# ME433_First_PCB.net
KiCad netlist of a schematic drawn in EAGLE
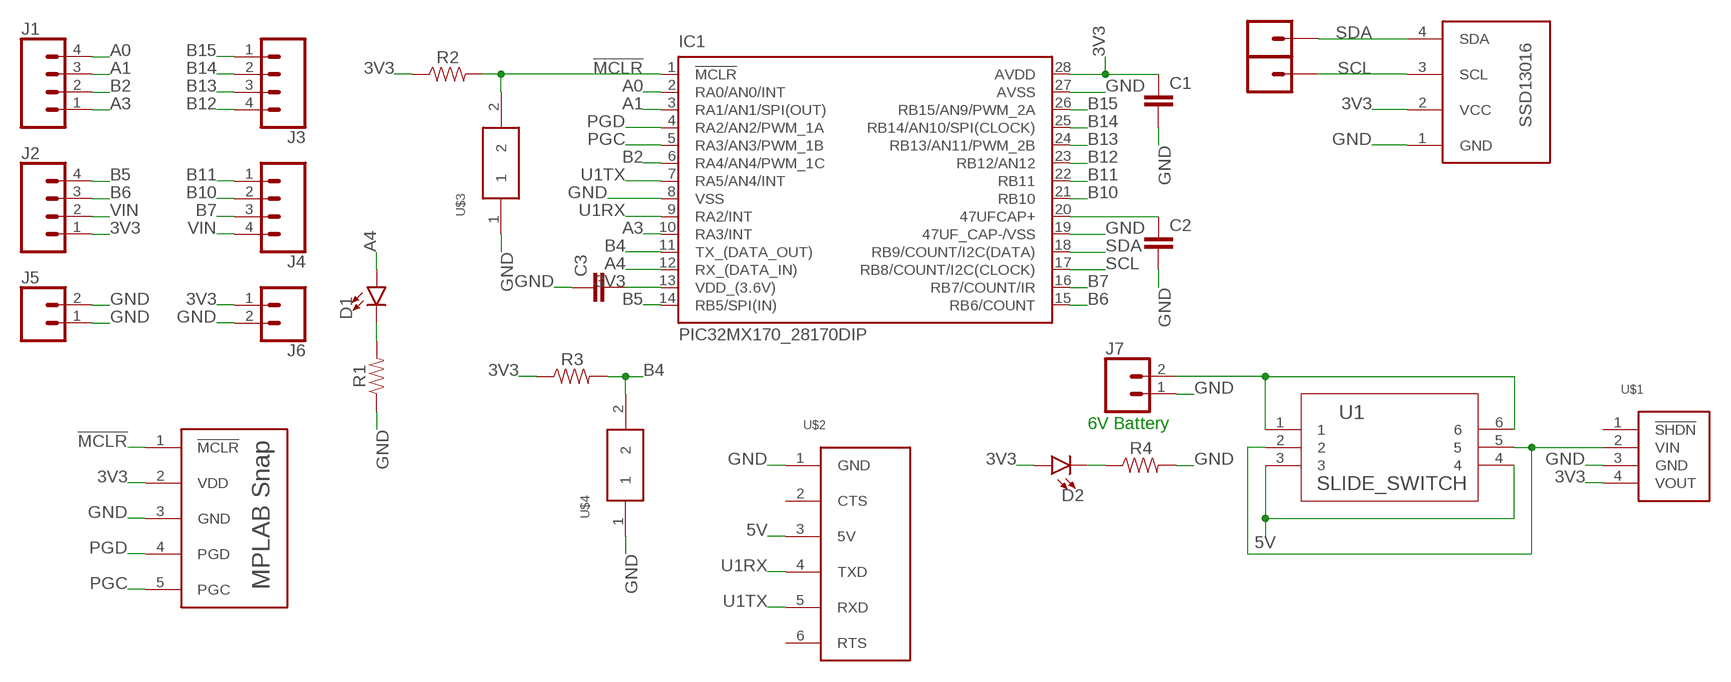
[diagram p0: schematic, sheet 1]

(export (version "E")
  (design (tool "Eeschema 10.0.6"))
  (components
    (comp (ref "C1")
      (value "C-EU025-025X050")
      (footprint "eagle-import:C025-025X050")
      (libsource (lib "eagle-import") (part "C-EU025-025X050"))
    )
    (comp (ref "C2")
      (value "C-EU025-025X050")
      (footprint "eagle-import:C025-025X050")
      (libsource (lib "eagle-import") (part "C-EU025-025X050"))
    )
    (comp (ref "C3")
      (value "C-EU025-025X050")
      (footprint "eagle-import:C025-025X050")
      (libsource (lib "eagle-import") (part "C-EU025-025X050"))
    )
    (comp (ref "D1")
      (value "LED3MM")
      (footprint "eagle-import:LED_3MM")
      (libsource (lib "eagle-import") (part "LED3MM"))
    )
    (comp (ref "D2")
      (value "LED3MM")
      (footprint "eagle-import:LED_3MM")
      (libsource (lib "eagle-import") (part "LED3MM"))
    )
    (comp (ref "IC1")
      (value "PIC32MX170_28170DIP")
      (footprint "eagle-import:DIL28-3")
      (libsource (lib "eagle-import") (part "PIC32MX170_28DIP170"))
    )
    (comp (ref "J1")
      (value "CONN_04")
      (footprint "eagle-import:1X04")
      (libsource (lib "eagle-import") (part "CONN_04"))
    )
    (comp (ref "J2")
      (value "CONN_04")
      (footprint "eagle-import:1X04")
      (libsource (lib "eagle-import") (part "CONN_04"))
    )
    (comp (ref "J3")
      (value "CONN_04")
      (footprint "eagle-import:1X04")
      (libsource (lib "eagle-import") (part "CONN_04"))
    )
    (comp (ref "J4")
      (value "CONN_04")
      (footprint "eagle-import:1X04")
      (libsource (lib "eagle-import") (part "CONN_04"))
    )
    (comp (ref "J5")
      (value "CONN_02")
      (footprint "eagle-import:1X02")
      (libsource (lib "eagle-import") (part "CONN_02"))
    )
    (comp (ref "J6")
      (value "CONN_02")
      (footprint "eagle-import:1X02")
      (libsource (lib "eagle-import") (part "CONN_02"))
    )
    (comp (ref "J7")
      (value "CONN_02")
      (footprint "eagle-import:1X02")
      (libsource (lib "eagle-import") (part "CONN_02"))
    )
    (comp (ref "J8")
      (value "CONN_01")
      (footprint "eagle-import:1X01")
      (libsource (lib "eagle-import") (part "CONN_01"))
    )
    (comp (ref "J9")
      (value "CONN_01")
      (footprint "eagle-import:1X01")
      (libsource (lib "eagle-import") (part "CONN_01"))
    )
    (comp (ref "OLED")
      (value "OLED_SCREEN")
      (footprint "eagle-import:OLED_SCREEN")
      (libsource (lib "eagle-import") (part "OLED_SCREEN"))
    )
    (comp (ref "R1")
      (value "1M")
      (footprint "eagle-import:AXIAL-0.3")
      (libsource (lib "eagle-import") (part "1MOHM-HORIZ-1/4W-5%"))
    )
    (comp (ref "R2")
      (value "1M")
      (footprint "eagle-import:AXIAL-0.3")
      (libsource (lib "eagle-import") (part "1MOHM-HORIZ-1/4W-5%"))
    )
    (comp (ref "R3")
      (value "1M")
      (footprint "eagle-import:AXIAL-0.3")
      (libsource (lib "eagle-import") (part "1MOHM-HORIZ-1/4W-5%"))
    )
    (comp (ref "R4")
      (value "1M")
      (footprint "eagle-import:AXIAL-0.3")
      (libsource (lib "eagle-import") (part "1MOHM-HORIZ-1/4W-5%"))
    )
    (comp (ref "U$1")
      (value "POLOLU_3V3_VREG")
      (footprint "eagle-import:POLOLU_3V3_VREG")
      (libsource (lib "eagle-import") (part "POLOLU_3V3_VREG"))
    )
    (comp (ref "U$2")
      (value "ADAFRUIT_CP2104")
      (footprint "eagle-import:ADAFRUIT_CP2104")
      (libsource (lib "eagle-import") (part "ADAFRUIT_CP2104"))
    )
    (comp (ref "U$3")
      (value "BUTTON")
      (footprint "eagle-import:BUTTON")
      (libsource (lib "eagle-import") (part "BUTTON"))
    )
    (comp (ref "U$4")
      (value "BUTTON")
      (footprint "eagle-import:BUTTON")
      (libsource (lib "eagle-import") (part "BUTTON"))
    )
    (comp (ref "U$5")
      (value "MPLAB_SNAP")
      (footprint "eagle-import:MPLAB_SNAP")
      (libsource (lib "eagle-import") (part "MPLAB_SNAP"))
    )
    (comp (ref "U1")
      (value "SLIDE_SWITCH")
      (footprint "eagle-import:SWITCH_011CQN")
      (fields
        (field (name "MANUFACTURER_PART_NUMBER") "JS202011CQN")
        (field (name "COPYRIGHT") "Copyright (C) 2022 Ultra Librarian. All rights reserved.")
      )
      (libsource (lib "eagle-import") (part "SLIDE_SWITCH"))
    )
  )
  (nets
    (net (code "1") (name "/3V3") (class "Default")
      (node (ref "C1") (pin "1") (pinfunction "1_1") (pintype "passive"))
      (node (ref "C3") (pin "2") (pinfunction "2_2") (pintype "passive"))
      (node (ref "D2") (pin "A") (pinfunction "A_A") (pintype "passive"))
      (node (ref "IC1") (pin "13") (pinfunction "VDD_(3.6V)_13") (pintype "bidirectional"))
      (node (ref "IC1") (pin "28") (pinfunction "AVDD_28") (pintype "bidirectional"))
      (node (ref "J2") (pin "1") (pinfunction "1_1") (pintype "passive"))
      (node (ref "J6") (pin "1") (pinfunction "1_1") (pintype "passive"))
      (node (ref "OLED") (pin "2") (pinfunction "VCC_2") (pintype "bidirectional"))
      (node (ref "R2") (pin "P$1") (pinfunction "1_P$1") (pintype "passive"))
      (node (ref "R3") (pin "P$1") (pinfunction "1_P$1") (pintype "passive"))
      (node (ref "U$1") (pin "4") (pinfunction "VOUT_4") (pintype "passive"))
      (node (ref "U$5") (pin "2") (pinfunction "VDD_2") (pintype "bidirectional"))
    )
    (net (code "2") (name "/5V") (class "Default")
      (node (ref "U$2") (pin "3") (pinfunction "5V_3") (pintype "bidirectional"))
      (node (ref "U1") (pin "3") (pinfunction "3_3") (pintype "passive"))
      (node (ref "U1") (pin "4") (pinfunction "4_4") (pintype "passive"))
    )
    (net (code "3") (name "/A0") (class "Default")
      (node (ref "IC1") (pin "2") (pinfunction "RA0/AN0/INT_2") (pintype "bidirectional"))
      (node (ref "J1") (pin "4") (pinfunction "4_4") (pintype "passive"))
    )
    (net (code "4") (name "/A1") (class "Default")
      (node (ref "IC1") (pin "3") (pinfunction "RA1/AN1/SPI(OUT)_3") (pintype "bidirectional"))
      (node (ref "J1") (pin "3") (pinfunction "3_3") (pintype "passive"))
    )
    (net (code "5") (name "/A3") (class "Default")
      (node (ref "IC1") (pin "10") (pinfunction "RA3/INT_10") (pintype "output"))
      (node (ref "J1") (pin "1") (pinfunction "1_1") (pintype "passive"))
    )
    (net (code "6") (name "/A4") (class "Default")
      (node (ref "D1") (pin "A") (pinfunction "A_A") (pintype "passive"))
      (node (ref "IC1") (pin "12") (pinfunction "RX_(DATA_IN)_12") (pintype "bidirectional"))
    )
    (net (code "7") (name "/B2") (class "Default")
      (node (ref "IC1") (pin "6") (pinfunction "RA4/AN4/PWM_1C_6") (pintype "bidirectional"))
      (node (ref "J1") (pin "2") (pinfunction "2_2") (pintype "passive"))
    )
    (net (code "8") (name "/B4") (class "Default")
      (node (ref "IC1") (pin "11") (pinfunction "TX_(DATA_OUT)_11") (pintype "bidirectional"))
      (node (ref "R3") (pin "P$2") (pinfunction "2_P$2") (pintype "passive"))
      (node (ref "U$4") (pin "2") (pinfunction "2_2") (pintype "bidirectional"))
    )
    (net (code "9") (name "/B5") (class "Default")
      (node (ref "IC1") (pin "14") (pinfunction "RB5/SPI(IN)_14") (pintype "bidirectional"))
      (node (ref "J2") (pin "4") (pinfunction "4_4") (pintype "passive"))
    )
    (net (code "10") (name "/B6") (class "Default")
      (node (ref "IC1") (pin "15") (pinfunction "RB6/COUNT_15") (pintype "bidirectional"))
      (node (ref "J2") (pin "3") (pinfunction "3_3") (pintype "passive"))
    )
    (net (code "11") (name "/B7") (class "Default")
      (node (ref "IC1") (pin "16") (pinfunction "RB7/COUNT/IR_16") (pintype "bidirectional"))
      (node (ref "J4") (pin "3") (pinfunction "3_3") (pintype "passive"))
    )
    (net (code "12") (name "/B10") (class "Default")
      (node (ref "IC1") (pin "21") (pinfunction "RB10_21") (pintype "bidirectional"))
      (node (ref "J4") (pin "2") (pinfunction "2_2") (pintype "passive"))
    )
    (net (code "13") (name "/B11") (class "Default")
      (node (ref "IC1") (pin "22") (pinfunction "RB11_22") (pintype "bidirectional"))
      (node (ref "J4") (pin "1") (pinfunction "1_1") (pintype "passive"))
    )
    (net (code "14") (name "/B12") (class "Default")
      (node (ref "IC1") (pin "23") (pinfunction "RB12/AN12_23") (pintype "bidirectional"))
      (node (ref "J3") (pin "4") (pinfunction "4_4") (pintype "passive"))
    )
    (net (code "15") (name "/B13") (class "Default")
      (node (ref "IC1") (pin "24") (pinfunction "RB13/AN11/PWM_2B_24") (pintype "bidirectional"))
      (node (ref "J3") (pin "3") (pinfunction "3_3") (pintype "passive"))
    )
    (net (code "16") (name "/B14") (class "Default")
      (node (ref "IC1") (pin "25") (pinfunction "RB14/AN10/SPI(CLOCK)_25") (pintype "bidirectional"))
      (node (ref "J3") (pin "2") (pinfunction "2_2") (pintype "passive"))
    )
    (net (code "17") (name "/B15") (class "Default")
      (node (ref "IC1") (pin "26") (pinfunction "RB15/AN9/PWM_2A_26") (pintype "bidirectional"))
      (node (ref "J3") (pin "1") (pinfunction "1_1") (pintype "passive"))
    )
    (net (code "18") (name "/GND") (class "Default")
      (node (ref "C1") (pin "2") (pinfunction "2_2") (pintype "passive"))
      (node (ref "C2") (pin "2") (pinfunction "2_2") (pintype "passive"))
      (node (ref "C3") (pin "1") (pinfunction "1_1") (pintype "passive"))
      (node (ref "IC1") (pin "19") (pinfunction "47UF_CAP-/VSS_19") (pintype "power_in"))
      (node (ref "IC1") (pin "27") (pinfunction "AVSS_27") (pintype "bidirectional"))
      (node (ref "IC1") (pin "8") (pinfunction "VSS_8") (pintype "power_in"))
      (node (ref "J5") (pin "1") (pinfunction "1_1") (pintype "passive"))
      (node (ref "J5") (pin "2") (pinfunction "2_2") (pintype "passive"))
      (node (ref "J6") (pin "2") (pinfunction "2_2") (pintype "passive"))
      (node (ref "J7") (pin "1") (pinfunction "1_1") (pintype "passive"))
      (node (ref "OLED") (pin "1") (pinfunction "GND_1") (pintype "bidirectional"))
      (node (ref "R1") (pin "P$1") (pinfunction "1_P$1") (pintype "passive"))
      (node (ref "R4") (pin "P$2") (pinfunction "2_P$2") (pintype "passive"))
      (node (ref "U$1") (pin "3") (pinfunction "GND_3") (pintype "passive"))
      (node (ref "U$2") (pin "1") (pinfunction "GND_1") (pintype "bidirectional"))
      (node (ref "U$3") (pin "1") (pinfunction "1_1") (pintype "bidirectional"))
      (node (ref "U$4") (pin "1") (pinfunction "1_1") (pintype "bidirectional"))
      (node (ref "U$5") (pin "3") (pinfunction "GND_3") (pintype "bidirectional"))
    )
    (net (code "19") (name "/PGC") (class "Default")
      (node (ref "IC1") (pin "5") (pinfunction "RA3/AN3/PWM_1B_5") (pintype "bidirectional"))
      (node (ref "U$5") (pin "5") (pinfunction "PGC_5") (pintype "bidirectional"))
    )
    (net (code "20") (name "/PGD") (class "Default")
      (node (ref "IC1") (pin "4") (pinfunction "RA2/AN2/PWM_1A_4") (pintype "bidirectional"))
      (node (ref "U$5") (pin "4") (pinfunction "PGD_4") (pintype "bidirectional"))
    )
    (net (code "21") (name "/SCL") (class "Default")
      (node (ref "IC1") (pin "17") (pinfunction "RB8/COUNT/I2C(CLOCK)_17") (pintype "bidirectional"))
      (node (ref "J9") (pin "1") (pinfunction "1_1") (pintype "passive"))
      (node (ref "OLED") (pin "3") (pinfunction "SCL_3") (pintype "bidirectional"))
    )
    (net (code "22") (name "/SDA") (class "Default")
      (node (ref "IC1") (pin "18") (pinfunction "RB9/COUNT/I2C(DATA)_18") (pintype "bidirectional"))
      (node (ref "J8") (pin "1") (pinfunction "1_1") (pintype "passive"))
      (node (ref "OLED") (pin "4") (pinfunction "SDA_4") (pintype "bidirectional"))
    )
    (net (code "23") (name "/U1RX") (class "Default")
      (node (ref "IC1") (pin "9") (pinfunction "RA2/INT_9") (pintype "input"))
      (node (ref "U$2") (pin "4") (pinfunction "TXD_4") (pintype "bidirectional"))
    )
    (net (code "24") (name "/U1TX") (class "Default")
      (node (ref "IC1") (pin "7") (pinfunction "RA5/AN4/INT_7") (pintype "bidirectional"))
      (node (ref "U$2") (pin "5") (pinfunction "RXD_5") (pintype "bidirectional"))
    )
    (net (code "25") (name "/VIN") (class "Default")
      (node (ref "J2") (pin "2") (pinfunction "2_2") (pintype "passive"))
      (node (ref "J4") (pin "4") (pinfunction "4_4") (pintype "passive"))
      (node (ref "U$1") (pin "2") (pinfunction "VIN_2") (pintype "passive"))
      (node (ref "U1") (pin "2") (pinfunction "2_2") (pintype "passive"))
      (node (ref "U1") (pin "5") (pinfunction "5_5") (pintype "passive"))
    )
    (net (code "26") (name "/~{MCLR}") (class "Default")
      (node (ref "IC1") (pin "1") (pinfunction "~{MCLR}_1") (pintype "input"))
      (node (ref "R2") (pin "P$2") (pinfunction "2_P$2") (pintype "passive"))
      (node (ref "U$3") (pin "2") (pinfunction "2_2") (pintype "bidirectional"))
      (node (ref "U$5") (pin "1") (pinfunction "~{MCLR}_1") (pintype "bidirectional"))
    )
    (net (code "27") (name "Net-(D1-C)") (class "Default")
      (node (ref "D1") (pin "K") (pinfunction "C_K") (pintype "passive"))
      (node (ref "R1") (pin "P$2") (pinfunction "2_P$2") (pintype "passive"))
    )
    (net (code "28") (name "Net-(D2-C)") (class "Default")
      (node (ref "D2") (pin "K") (pinfunction "C_K") (pintype "passive"))
      (node (ref "R4") (pin "P$1") (pinfunction "1_P$1") (pintype "passive"))
    )
    (net (code "29") (name "Net-(IC1-47UFCAP+)") (class "Default")
      (node (ref "C2") (pin "1") (pinfunction "1_1") (pintype "passive"))
      (node (ref "IC1") (pin "20") (pinfunction "47UFCAP+_20") (pintype "power_in"))
    )
    (net (code "30") (name "Net-(J7-Pad2)") (class "Default")
      (node (ref "J7") (pin "2") (pinfunction "2_2") (pintype "passive"))
      (node (ref "U1") (pin "1") (pinfunction "1_1") (pintype "passive"))
      (node (ref "U1") (pin "6") (pinfunction "6_6") (pintype "passive"))
    )
    (net (code "31") (name "unconnected-(U$1-~{SHDN}-Pad1)") (class "Default")
      (node (ref "U$1") (pin "1") (pinfunction "~{SHDN}_1") (pintype "passive"))
    )
    (net (code "32") (name "unconnected-(U$2-CTS-Pad2)") (class "Default")
      (node (ref "U$2") (pin "2") (pinfunction "CTS_2") (pintype "bidirectional"))
    )
    (net (code "33") (name "unconnected-(U$2-RTS-Pad6)") (class "Default")
      (node (ref "U$2") (pin "6") (pinfunction "RTS_6") (pintype "bidirectional"))
    )
  )
)
